# PSU-triple-voltage-eagle-6.net
KiCad netlist of a schematic drawn in EAGLE
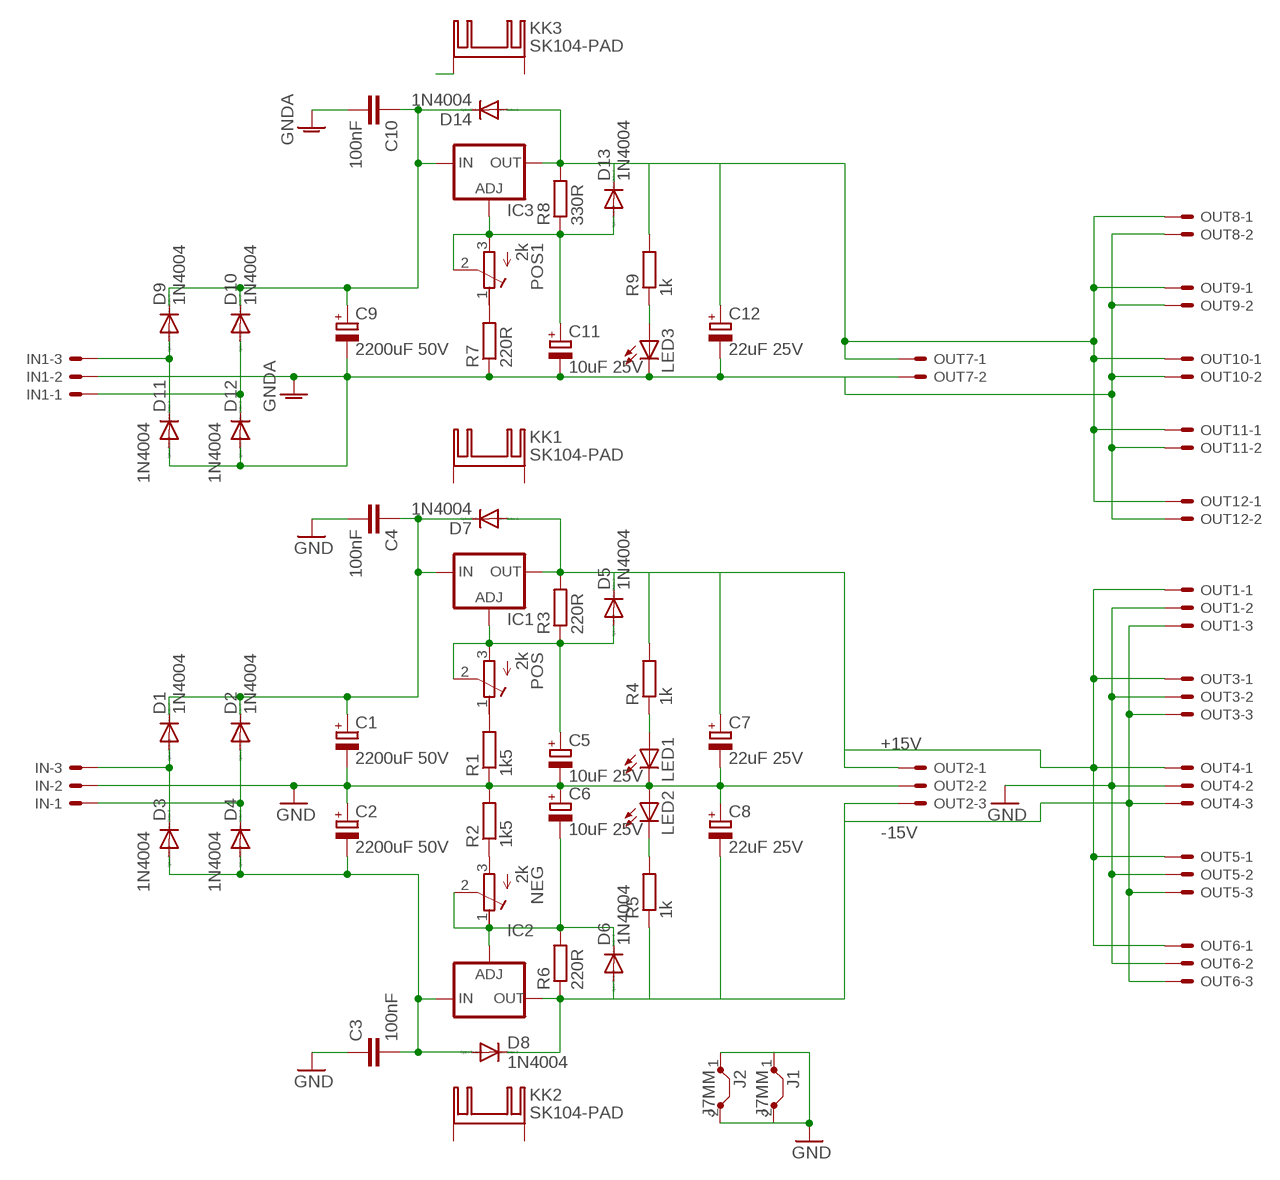
[diagram p0: schematic, sheet 1]

(export (version "E")
  (design (tool "Eeschema 10.0.6"))
  (components
    (comp (ref "C1")
      (value "2200uF 50V")
      (footprint "eagle-import:E7,5-16")
      (libsource (lib "eagle-import") (part "CPOL-EUE7.5-16"))
    )
    (comp (ref "C2")
      (value "2200uF 50V")
      (footprint "eagle-import:E7,5-16")
      (libsource (lib "eagle-import") (part "CPOL-EUE7.5-16"))
    )
    (comp (ref "C3")
      (value "100nF")
      (footprint "eagle-import:C050-025X075")
      (libsource (lib "eagle-import") (part "C-EU050-025X075"))
    )
    (comp (ref "C4")
      (value "100nF")
      (footprint "eagle-import:C050-025X075")
      (libsource (lib "eagle-import") (part "C-EU050-025X075"))
    )
    (comp (ref "C5")
      (value "10uF 25V")
      (footprint "eagle-import:E2,5-5")
      (libsource (lib "eagle-import") (part "CPOL-EUE2.5-5"))
    )
    (comp (ref "C6")
      (value "10uF 25V")
      (footprint "eagle-import:E2,5-5")
      (libsource (lib "eagle-import") (part "CPOL-EUE2.5-5"))
    )
    (comp (ref "C7")
      (value "22uF 25V")
      (footprint "eagle-import:E2,5-5")
      (libsource (lib "eagle-import") (part "CPOL-EUE2.5-5"))
    )
    (comp (ref "C8")
      (value "22uF 25V")
      (footprint "eagle-import:E2,5-5")
      (libsource (lib "eagle-import") (part "CPOL-EUE2.5-5"))
    )
    (comp (ref "C9")
      (value "2200uF 50V")
      (footprint "eagle-import:E7,5-16")
      (libsource (lib "eagle-import") (part "CPOL-EUE7.5-16"))
    )
    (comp (ref "C10")
      (value "100nF")
      (footprint "eagle-import:C050-025X075")
      (libsource (lib "eagle-import") (part "C-EU050-025X075"))
    )
    (comp (ref "C11")
      (value "10uF 25V")
      (footprint "eagle-import:E2,5-5")
      (libsource (lib "eagle-import") (part "CPOL-EUE2.5-5"))
    )
    (comp (ref "C12")
      (value "22uF 25V")
      (footprint "eagle-import:E2,5-5")
      (libsource (lib "eagle-import") (part "CPOL-EUE2.5-5"))
    )
    (comp (ref "D1")
      (value "1N4004")
      (footprint "eagle-import:DO41-10")
      (libsource (lib "eagle-import") (part "1N4004"))
    )
    (comp (ref "D2")
      (value "1N4004")
      (footprint "eagle-import:DO41-10")
      (libsource (lib "eagle-import") (part "1N4004"))
    )
    (comp (ref "D3")
      (value "1N4004")
      (footprint "eagle-import:DO41-10")
      (libsource (lib "eagle-import") (part "1N4004"))
    )
    (comp (ref "D4")
      (value "1N4004")
      (footprint "eagle-import:DO41-10")
      (libsource (lib "eagle-import") (part "1N4004"))
    )
    (comp (ref "D5")
      (value "1N4004")
      (footprint "eagle-import:DO41-10")
      (libsource (lib "eagle-import") (part "1N4004"))
    )
    (comp (ref "D6")
      (value "1N4004")
      (footprint "eagle-import:DO41-10")
      (libsource (lib "eagle-import") (part "1N4004"))
    )
    (comp (ref "D7")
      (value "1N4004")
      (footprint "eagle-import:DO41-10")
      (libsource (lib "eagle-import") (part "1N4004"))
    )
    (comp (ref "D8")
      (value "1N4004")
      (footprint "eagle-import:DO41-10")
      (libsource (lib "eagle-import") (part "1N4004"))
    )
    (comp (ref "D9")
      (value "1N4004")
      (footprint "eagle-import:DO41-10")
      (libsource (lib "eagle-import") (part "1N4004"))
    )
    (comp (ref "D10")
      (value "1N4004")
      (footprint "eagle-import:DO41-10")
      (libsource (lib "eagle-import") (part "1N4004"))
    )
    (comp (ref "D11")
      (value "1N4004")
      (footprint "eagle-import:DO41-10")
      (libsource (lib "eagle-import") (part "1N4004"))
    )
    (comp (ref "D12")
      (value "1N4004")
      (footprint "eagle-import:DO41-10")
      (libsource (lib "eagle-import") (part "1N4004"))
    )
    (comp (ref "D13")
      (value "1N4004")
      (footprint "eagle-import:DO41-10")
      (libsource (lib "eagle-import") (part "1N4004"))
    )
    (comp (ref "D14")
      (value "1N4004")
      (footprint "eagle-import:DO41-10")
      (libsource (lib "eagle-import") (part "1N4004"))
    )
    (comp (ref "IC1")
      (value "LM317TS")
      (footprint "eagle-import:317TS")
      (libsource (lib "eagle-import") (part "LM317TS"))
    )
    (comp (ref "IC2")
      (value "LM337TS")
      (footprint "eagle-import:337TS")
      (libsource (lib "eagle-import") (part "LM337TS"))
    )
    (comp (ref "IC3")
      (value "LM317TS")
      (footprint "eagle-import:317TS")
      (libsource (lib "eagle-import") (part "LM317TS"))
    )
    (comp (ref "IN")
      (value "KK-156-3")
      (footprint "eagle-import:KK-156-3")
      (libsource (lib "eagle-import") (part "KK-156-3"))
    )
    (comp (ref "IN1")
      (value "KK-156-3")
      (footprint "eagle-import:KK-156-3")
      (libsource (lib "eagle-import") (part "KK-156-3"))
    )
    (comp (ref "J1")
      (value "J7MM")
      (footprint "eagle-import:07")
      (libsource (lib "eagle-import") (part "J7MM"))
    )
    (comp (ref "J2")
      (value "J7MM")
      (footprint "eagle-import:07")
      (libsource (lib "eagle-import") (part "J7MM"))
    )
    (comp (ref "KK1")
      (value "SK104-PAD")
      (footprint "eagle-import:SK104-PAD")
      (libsource (lib "eagle-import") (part "SK104-PAD"))
    )
    (comp (ref "KK2")
      (value "SK104-PAD")
      (footprint "eagle-import:SK104-PAD")
      (libsource (lib "eagle-import") (part "SK104-PAD"))
    )
    (comp (ref "KK3")
      (value "SK104-PAD")
      (footprint "eagle-import:SK104-PAD")
      (libsource (lib "eagle-import") (part "SK104-PAD"))
    )
    (comp (ref "LED1")
      (value "LED3MM")
      (footprint "eagle-import:LED3MM")
      (libsource (lib "eagle-import") (part "LED3MM"))
    )
    (comp (ref "LED2")
      (value "LED3MM")
      (footprint "eagle-import:LED3MM")
      (libsource (lib "eagle-import") (part "LED3MM"))
    )
    (comp (ref "LED3")
      (value "LED3MM")
      (footprint "eagle-import:LED3MM")
      (libsource (lib "eagle-import") (part "LED3MM"))
    )
    (comp (ref "NEG")
      (value "2k")
      (footprint "eagle-import:RTRIMT93YA")
      (libsource (lib "eagle-import") (part "R-TRIMMT93YA"))
    )
    (comp (ref "OUT1")
      (value "KK-156-3")
      (footprint "eagle-import:KK-156-3")
      (libsource (lib "eagle-import") (part "KK-156-3"))
    )
    (comp (ref "OUT2")
      (value "KK-156-3")
      (footprint "eagle-import:KK-156-3")
      (libsource (lib "eagle-import") (part "KK-156-3"))
    )
    (comp (ref "OUT3")
      (value "KK-156-3")
      (footprint "eagle-import:KK-156-3")
      (libsource (lib "eagle-import") (part "KK-156-3"))
    )
    (comp (ref "OUT4")
      (value "KK-156-3")
      (footprint "eagle-import:KK-156-3")
      (libsource (lib "eagle-import") (part "KK-156-3"))
    )
    (comp (ref "OUT5")
      (value "KK-156-3")
      (footprint "eagle-import:KK-156-3")
      (libsource (lib "eagle-import") (part "KK-156-3"))
    )
    (comp (ref "OUT6")
      (value "KK-156-3")
      (footprint "eagle-import:KK-156-3")
      (libsource (lib "eagle-import") (part "KK-156-3"))
    )
    (comp (ref "OUT7")
      (value "KK-156-2")
      (footprint "eagle-import:KK-156-2")
      (libsource (lib "eagle-import") (part "KK-156-2"))
    )
    (comp (ref "OUT8")
      (value "KK-156-2")
      (footprint "eagle-import:KK-156-2")
      (libsource (lib "eagle-import") (part "KK-156-2"))
    )
    (comp (ref "OUT9")
      (value "KK-156-2")
      (footprint "eagle-import:KK-156-2")
      (libsource (lib "eagle-import") (part "KK-156-2"))
    )
    (comp (ref "OUT10")
      (value "KK-156-2")
      (footprint "eagle-import:KK-156-2")
      (libsource (lib "eagle-import") (part "KK-156-2"))
    )
    (comp (ref "OUT11")
      (value "KK-156-2")
      (footprint "eagle-import:KK-156-2")
      (libsource (lib "eagle-import") (part "KK-156-2"))
    )
    (comp (ref "OUT12")
      (value "KK-156-2")
      (footprint "eagle-import:KK-156-2")
      (libsource (lib "eagle-import") (part "KK-156-2"))
    )
    (comp (ref "POS")
      (value "2k")
      (footprint "eagle-import:RTRIMT93YA")
      (libsource (lib "eagle-import") (part "R-TRIMMT93YA"))
    )
    (comp (ref "POS1")
      (value "2k")
      (footprint "eagle-import:RTRIMT93YA")
      (libsource (lib "eagle-import") (part "R-TRIMMT93YA"))
    )
    (comp (ref "R1")
      (value "1k5")
      (footprint "eagle-import:0207_7")
      (libsource (lib "eagle-import") (part "R-EU_0207/7"))
    )
    (comp (ref "R2")
      (value "1k5")
      (footprint "eagle-import:0207_7")
      (libsource (lib "eagle-import") (part "R-EU_0207/7"))
    )
    (comp (ref "R3")
      (value "220R")
      (footprint "eagle-import:0207_7")
      (libsource (lib "eagle-import") (part "R-EU_0207/7"))
    )
    (comp (ref "R4")
      (value "1k")
      (footprint "eagle-import:0207_7")
      (libsource (lib "eagle-import") (part "R-EU_0207/7"))
    )
    (comp (ref "R5")
      (value "1k")
      (footprint "eagle-import:0207_7")
      (libsource (lib "eagle-import") (part "R-EU_0207/7"))
    )
    (comp (ref "R6")
      (value "220R")
      (footprint "eagle-import:0207_7")
      (libsource (lib "eagle-import") (part "R-EU_0207/7"))
    )
    (comp (ref "R7")
      (value "220R")
      (footprint "eagle-import:0207_7")
      (libsource (lib "eagle-import") (part "R-EU_0207/7"))
    )
    (comp (ref "R8")
      (value "330R")
      (footprint "eagle-import:0207_7")
      (libsource (lib "eagle-import") (part "R-EU_0207/7"))
    )
    (comp (ref "R9")
      (value "1k")
      (footprint "eagle-import:0207_7")
      (libsource (lib "eagle-import") (part "R-EU_0207/7"))
    )
  )
  (nets
    (net (code "1") (name "/+15V") (class "Default")
      (node (ref "C7") (pin "+") (pinfunction "+_+") (pintype "passive"))
      (node (ref "D5") (pin "C") (pinfunction "C_C") (pintype "passive"))
      (node (ref "D7") (pin "A") (pinfunction "A_A") (pintype "passive"))
      (node (ref "IC1") (pin "2") (pinfunction "OUT_2") (pintype "passive"))
      (node (ref "OUT1") (pin "1") (pinfunction "S_1") (pintype "passive"))
      (node (ref "OUT2") (pin "1") (pinfunction "S_1") (pintype "passive"))
      (node (ref "OUT3") (pin "1") (pinfunction "S_1") (pintype "passive"))
      (node (ref "OUT4") (pin "1") (pinfunction "S_1") (pintype "passive"))
      (node (ref "OUT5") (pin "1") (pinfunction "S_1") (pintype "passive"))
      (node (ref "OUT6") (pin "1") (pinfunction "S_1") (pintype "passive"))
      (node (ref "R3") (pin "2") (pinfunction "2_2") (pintype "passive"))
      (node (ref "R4") (pin "2") (pinfunction "2_2") (pintype "passive"))
    )
    (net (code "2") (name "/-15V") (class "Default")
      (node (ref "C8") (pin "-") (pinfunction "-_-") (pintype "passive"))
      (node (ref "D6") (pin "A") (pinfunction "A_A") (pintype "passive"))
      (node (ref "D8") (pin "C") (pinfunction "C_C") (pintype "passive"))
      (node (ref "IC2") (pin "3") (pinfunction "OUT_3") (pintype "passive"))
      (node (ref "OUT1") (pin "3") (pinfunction "S_3") (pintype "passive"))
      (node (ref "OUT2") (pin "3") (pinfunction "S_3") (pintype "passive"))
      (node (ref "OUT3") (pin "3") (pinfunction "S_3") (pintype "passive"))
      (node (ref "OUT4") (pin "3") (pinfunction "S_3") (pintype "passive"))
      (node (ref "OUT5") (pin "3") (pinfunction "S_3") (pintype "passive"))
      (node (ref "OUT6") (pin "3") (pinfunction "S_3") (pintype "passive"))
      (node (ref "R5") (pin "1") (pinfunction "1_1") (pintype "passive"))
      (node (ref "R6") (pin "1") (pinfunction "1_1") (pintype "passive"))
    )
    (net (code "3") (name "GND") (class "Default")
      (node (ref "C1") (pin "-") (pinfunction "-_-") (pintype "passive"))
      (node (ref "C2") (pin "+") (pinfunction "+_+") (pintype "passive"))
      (node (ref "C3") (pin "1") (pinfunction "1_1") (pintype "passive"))
      (node (ref "C4") (pin "2") (pinfunction "2_2") (pintype "passive"))
      (node (ref "C5") (pin "-") (pinfunction "-_-") (pintype "passive"))
      (node (ref "C6") (pin "+") (pinfunction "+_+") (pintype "passive"))
      (node (ref "C7") (pin "-") (pinfunction "-_-") (pintype "passive"))
      (node (ref "C8") (pin "+") (pinfunction "+_+") (pintype "passive"))
      (node (ref "IN") (pin "2") (pinfunction "S_2") (pintype "passive"))
      (node (ref "J1") (pin "1") (pinfunction "1_1") (pintype "passive"))
      (node (ref "J1") (pin "2") (pinfunction "2_2") (pintype "passive"))
      (node (ref "J2") (pin "1") (pinfunction "1_1") (pintype "passive"))
      (node (ref "J2") (pin "2") (pinfunction "2_2") (pintype "passive"))
      (node (ref "LED1") (pin "K") (pinfunction "C_K") (pintype "passive"))
      (node (ref "LED2") (pin "A") (pinfunction "A_A") (pintype "passive"))
      (node (ref "OUT1") (pin "2") (pinfunction "S_2") (pintype "passive"))
      (node (ref "OUT2") (pin "2") (pinfunction "S_2") (pintype "passive"))
      (node (ref "OUT3") (pin "2") (pinfunction "S_2") (pintype "passive"))
      (node (ref "OUT4") (pin "2") (pinfunction "S_2") (pintype "passive"))
      (node (ref "OUT5") (pin "2") (pinfunction "S_2") (pintype "passive"))
      (node (ref "OUT6") (pin "2") (pinfunction "S_2") (pintype "passive"))
      (node (ref "R1") (pin "1") (pinfunction "1_1") (pintype "passive"))
      (node (ref "R2") (pin "2") (pinfunction "2_2") (pintype "passive"))
    )
    (net (code "4") (name "GNDA") (class "Default")
      (node (ref "C10") (pin "2") (pinfunction "2_2") (pintype "passive"))
      (node (ref "C11") (pin "-") (pinfunction "-_-") (pintype "passive"))
      (node (ref "C12") (pin "-") (pinfunction "-_-") (pintype "passive"))
      (node (ref "C9") (pin "-") (pinfunction "-_-") (pintype "passive"))
      (node (ref "D11") (pin "A") (pinfunction "A_A") (pintype "passive"))
      (node (ref "D12") (pin "A") (pinfunction "A_A") (pintype "passive"))
      (node (ref "IN1") (pin "2") (pinfunction "S_2") (pintype "passive"))
      (node (ref "LED3") (pin "K") (pinfunction "C_K") (pintype "passive"))
      (node (ref "OUT10") (pin "2") (pinfunction "S_2") (pintype "passive"))
      (node (ref "OUT11") (pin "2") (pinfunction "S_2") (pintype "passive"))
      (node (ref "OUT12") (pin "2") (pinfunction "S_2") (pintype "passive"))
      (node (ref "OUT7") (pin "2") (pinfunction "S_2") (pintype "passive"))
      (node (ref "OUT8") (pin "2") (pinfunction "S_2") (pintype "passive"))
      (node (ref "OUT9") (pin "2") (pinfunction "S_2") (pintype "passive"))
      (node (ref "R7") (pin "1") (pinfunction "1_1") (pintype "passive"))
    )
    (net (code "5") (name "Net-(IC1-ADJ)") (class "Default")
      (node (ref "C5") (pin "+") (pinfunction "+_+") (pintype "passive"))
      (node (ref "D5") (pin "A") (pinfunction "A_A") (pintype "passive"))
      (node (ref "IC1") (pin "1") (pinfunction "ADJ_1") (pintype "input"))
      (node (ref "POS") (pin "2") (pinfunction "S_2") (pintype "passive"))
      (node (ref "POS") (pin "3") (pinfunction "A_3") (pintype "passive"))
      (node (ref "R3") (pin "1") (pinfunction "1_1") (pintype "passive"))
    )
    (net (code "6") (name "Net-(IC1-IN)") (class "Default")
      (node (ref "C1") (pin "+") (pinfunction "+_+") (pintype "passive"))
      (node (ref "C4") (pin "1") (pinfunction "1_1") (pintype "passive"))
      (node (ref "D1") (pin "C") (pinfunction "C_C") (pintype "passive"))
      (node (ref "D2") (pin "C") (pinfunction "C_C") (pintype "passive"))
      (node (ref "D7") (pin "C") (pinfunction "C_C") (pintype "passive"))
      (node (ref "IC1") (pin "3") (pinfunction "IN_3") (pintype "input"))
    )
    (net (code "7") (name "Net-(IC2-ADJ)") (class "Default")
      (node (ref "C6") (pin "-") (pinfunction "-_-") (pintype "passive"))
      (node (ref "D6") (pin "C") (pinfunction "C_C") (pintype "passive"))
      (node (ref "IC2") (pin "1") (pinfunction "ADJ_1") (pintype "input"))
      (node (ref "NEG") (pin "1") (pinfunction "E_1") (pintype "passive"))
      (node (ref "NEG") (pin "2") (pinfunction "S_2") (pintype "passive"))
      (node (ref "R6") (pin "2") (pinfunction "2_2") (pintype "passive"))
    )
    (net (code "8") (name "Net-(IC2-IN)") (class "Default")
      (node (ref "C2") (pin "-") (pinfunction "-_-") (pintype "passive"))
      (node (ref "C3") (pin "2") (pinfunction "2_2") (pintype "passive"))
      (node (ref "D3") (pin "A") (pinfunction "A_A") (pintype "passive"))
      (node (ref "D4") (pin "A") (pinfunction "A_A") (pintype "passive"))
      (node (ref "D8") (pin "A") (pinfunction "A_A") (pintype "passive"))
      (node (ref "IC2") (pin "2") (pinfunction "IN_2") (pintype "input"))
    )
    (net (code "9") (name "Net-(IC3-ADJ)") (class "Default")
      (node (ref "C11") (pin "+") (pinfunction "+_+") (pintype "passive"))
      (node (ref "D13") (pin "A") (pinfunction "A_A") (pintype "passive"))
      (node (ref "IC3") (pin "1") (pinfunction "ADJ_1") (pintype "input"))
      (node (ref "POS1") (pin "2") (pinfunction "S_2") (pintype "passive"))
      (node (ref "POS1") (pin "3") (pinfunction "A_3") (pintype "passive"))
      (node (ref "R8") (pin "1") (pinfunction "1_1") (pintype "passive"))
    )
    (net (code "10") (name "Net-(IC3-IN)") (class "Default")
      (node (ref "C10") (pin "1") (pinfunction "1_1") (pintype "passive"))
      (node (ref "C9") (pin "+") (pinfunction "+_+") (pintype "passive"))
      (node (ref "D10") (pin "C") (pinfunction "C_C") (pintype "passive"))
      (node (ref "D14") (pin "C") (pinfunction "C_C") (pintype "passive"))
      (node (ref "D9") (pin "C") (pinfunction "C_C") (pintype "passive"))
      (node (ref "IC3") (pin "3") (pinfunction "IN_3") (pintype "input"))
    )
    (net (code "11") (name "Net-(IC3-OUT)") (class "Default")
      (node (ref "C12") (pin "+") (pinfunction "+_+") (pintype "passive"))
      (node (ref "D13") (pin "C") (pinfunction "C_C") (pintype "passive"))
      (node (ref "D14") (pin "A") (pinfunction "A_A") (pintype "passive"))
      (node (ref "IC3") (pin "2") (pinfunction "OUT_2") (pintype "passive"))
      (node (ref "OUT10") (pin "1") (pinfunction "S_1") (pintype "passive"))
      (node (ref "OUT11") (pin "1") (pinfunction "S_1") (pintype "passive"))
      (node (ref "OUT12") (pin "1") (pinfunction "S_1") (pintype "passive"))
      (node (ref "OUT7") (pin "1") (pinfunction "S_1") (pintype "passive"))
      (node (ref "OUT8") (pin "1") (pinfunction "S_1") (pintype "passive"))
      (node (ref "OUT9") (pin "1") (pinfunction "S_1") (pintype "passive"))
      (node (ref "R8") (pin "2") (pinfunction "2_2") (pintype "passive"))
      (node (ref "R9") (pin "2") (pinfunction "2_2") (pintype "passive"))
    )
    (net (code "12") (name "Net-(IN1A-S)") (class "Default")
      (node (ref "D10") (pin "A") (pinfunction "A_A") (pintype "passive"))
      (node (ref "D12") (pin "C") (pinfunction "C_C") (pintype "passive"))
      (node (ref "IN1") (pin "1") (pinfunction "S_1") (pintype "passive"))
    )
    (net (code "13") (name "Net-(IN1C-S)") (class "Default")
      (node (ref "D11") (pin "C") (pinfunction "C_C") (pintype "passive"))
      (node (ref "D9") (pin "A") (pinfunction "A_A") (pintype "passive"))
      (node (ref "IN1") (pin "3") (pinfunction "S_3") (pintype "passive"))
    )
    (net (code "14") (name "Net-(INA-S)") (class "Default")
      (node (ref "D2") (pin "A") (pinfunction "A_A") (pintype "passive"))
      (node (ref "D4") (pin "C") (pinfunction "C_C") (pintype "passive"))
      (node (ref "IN") (pin "1") (pinfunction "S_1") (pintype "passive"))
    )
    (net (code "15") (name "Net-(INC-S)") (class "Default")
      (node (ref "D1") (pin "A") (pinfunction "A_A") (pintype "passive"))
      (node (ref "D3") (pin "C") (pinfunction "C_C") (pintype "passive"))
      (node (ref "IN") (pin "3") (pinfunction "S_3") (pintype "passive"))
    )
    (net (code "16") (name "Net-(LED1-PadA)") (class "Default")
      (node (ref "LED1") (pin "A") (pinfunction "A_A") (pintype "passive"))
      (node (ref "R4") (pin "1") (pinfunction "1_1") (pintype "passive"))
    )
    (net (code "17") (name "Net-(LED2-C)") (class "Default")
      (node (ref "LED2") (pin "K") (pinfunction "C_K") (pintype "passive"))
      (node (ref "R5") (pin "2") (pinfunction "2_2") (pintype "passive"))
    )
    (net (code "18") (name "Net-(LED3-PadA)") (class "Default")
      (node (ref "LED3") (pin "A") (pinfunction "A_A") (pintype "passive"))
      (node (ref "R9") (pin "1") (pinfunction "1_1") (pintype "passive"))
    )
    (net (code "19") (name "Net-(NEG-A)") (class "Default")
      (node (ref "NEG") (pin "3") (pinfunction "A_3") (pintype "passive"))
      (node (ref "R2") (pin "1") (pinfunction "1_1") (pintype "passive"))
    )
    (net (code "20") (name "Net-(POS-E)") (class "Default")
      (node (ref "POS") (pin "1") (pinfunction "E_1") (pintype "passive"))
      (node (ref "R1") (pin "2") (pinfunction "2_2") (pintype "passive"))
    )
    (net (code "21") (name "Net-(POS1-E)") (class "Default")
      (node (ref "POS1") (pin "1") (pinfunction "E_1") (pintype "passive"))
      (node (ref "R7") (pin "2") (pinfunction "2_2") (pintype "passive"))
    )
    (net (code "22") (name "unconnected-(KK1-K-PadK1)") (class "Default")
      (node (ref "KK1") (pin "K1") (pinfunction "K_K1") (pintype "passive"))
    )
    (net (code "23") (name "unconnected-(KK1-K-PadK2)") (class "Default")
      (node (ref "KK1") (pin "K2") (pinfunction "K_K2") (pintype "passive"))
    )
    (net (code "24") (name "unconnected-(KK2-K-PadK1)") (class "Default")
      (node (ref "KK2") (pin "K1") (pinfunction "K_K1") (pintype "passive"))
    )
    (net (code "25") (name "unconnected-(KK2-K-PadK2)") (class "Default")
      (node (ref "KK2") (pin "K2") (pinfunction "K_K2") (pintype "passive"))
    )
    (net (code "26") (name "unconnected-(KK3-K-PadK1)") (class "Default")
      (node (ref "KK3") (pin "K1") (pinfunction "K_K1") (pintype "passive"))
    )
    (net (code "27") (name "unconnected-(KK3-K-PadK2)") (class "Default")
      (node (ref "KK3") (pin "K2") (pinfunction "K_K2") (pintype "passive"))
    )
  )
)
